# Laser_Array_Temp_Low_BRD_V2_3.net
KiCad netlist of a schematic drawn in EAGLE
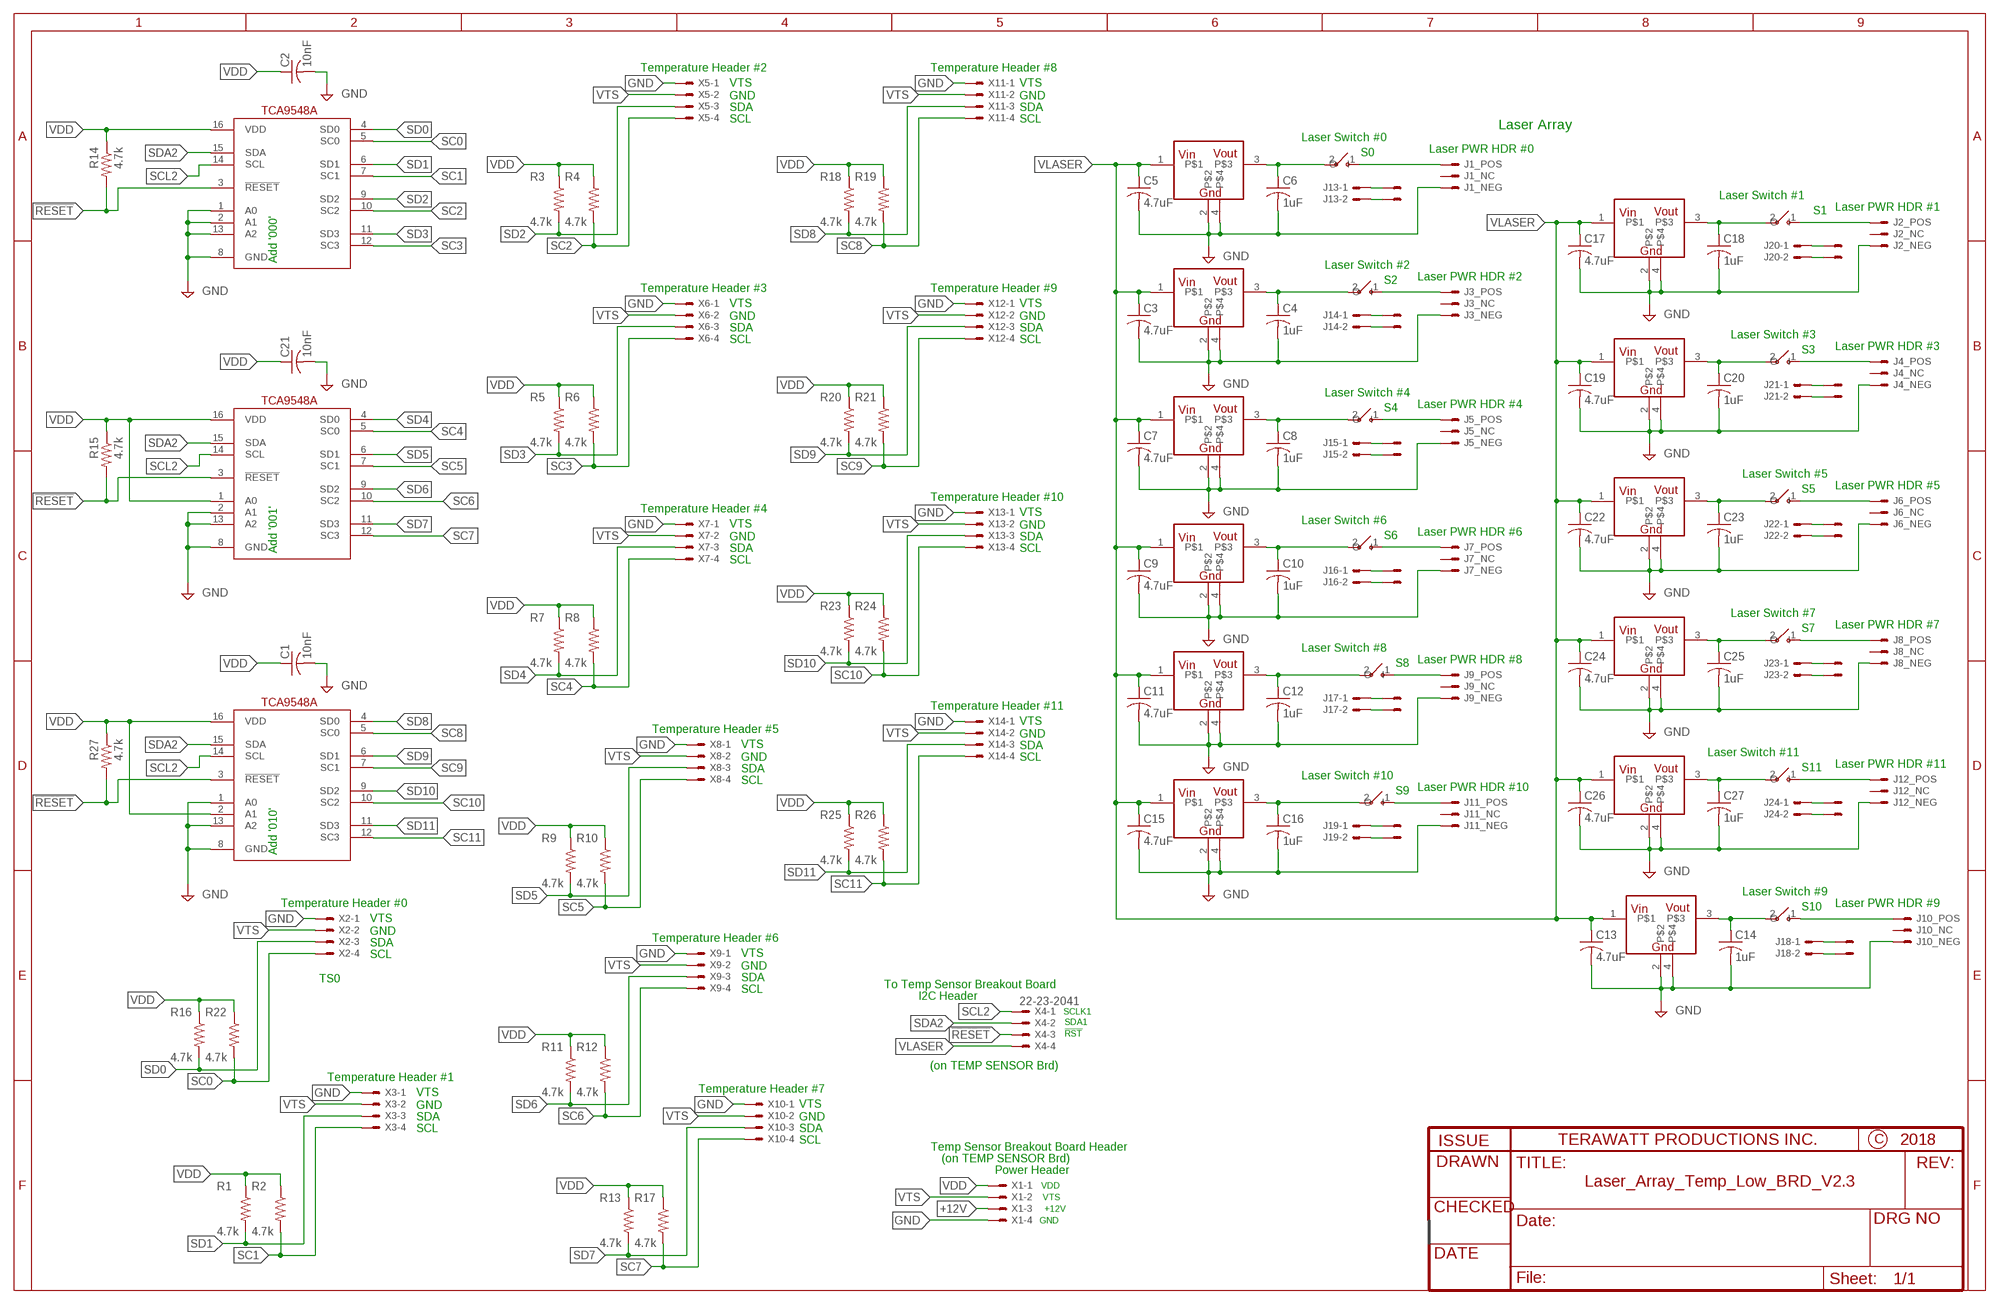
[diagram p0: schematic, sheet 1]

(export (version "E")
  (design (tool "Eeschema 10.0.6"))
  (components
    (comp (ref "C1")
      (value "10nF")
      (footprint "eagle-import:C0805")
      (libsource (lib "eagle-import") (part "C-USC0805"))
    )
    (comp (ref "C2")
      (value "10nF")
      (footprint "eagle-import:C0805")
      (libsource (lib "eagle-import") (part "C-USC0805"))
    )
    (comp (ref "C3")
      (value "4.7uF")
      (footprint "eagle-import:C0805")
      (libsource (lib "eagle-import") (part "C-USC0805"))
    )
    (comp (ref "C4")
      (value "1uF")
      (footprint "eagle-import:C0805")
      (libsource (lib "eagle-import") (part "C-USC0805"))
    )
    (comp (ref "C5")
      (value "4.7uF")
      (footprint "eagle-import:C0805")
      (libsource (lib "eagle-import") (part "C-USC0805"))
    )
    (comp (ref "C6")
      (value "1uF")
      (footprint "eagle-import:C0805")
      (libsource (lib "eagle-import") (part "C-USC0805"))
    )
    (comp (ref "C7")
      (value "4.7uF")
      (footprint "eagle-import:C0805")
      (libsource (lib "eagle-import") (part "C-USC0805"))
    )
    (comp (ref "C8")
      (value "1uF")
      (footprint "eagle-import:C0805")
      (libsource (lib "eagle-import") (part "C-USC0805"))
    )
    (comp (ref "C9")
      (value "4.7uF")
      (footprint "eagle-import:C0805")
      (libsource (lib "eagle-import") (part "C-USC0805"))
    )
    (comp (ref "C10")
      (value "1uF")
      (footprint "eagle-import:C0805")
      (libsource (lib "eagle-import") (part "C-USC0805"))
    )
    (comp (ref "C11")
      (value "4.7uF")
      (footprint "eagle-import:C0805")
      (libsource (lib "eagle-import") (part "C-USC0805"))
    )
    (comp (ref "C12")
      (value "1uF")
      (footprint "eagle-import:C0805")
      (libsource (lib "eagle-import") (part "C-USC0805"))
    )
    (comp (ref "C13")
      (value "4.7uF")
      (footprint "eagle-import:C0805")
      (libsource (lib "eagle-import") (part "C-USC0805"))
    )
    (comp (ref "C14")
      (value "1uF")
      (footprint "eagle-import:C0805")
      (libsource (lib "eagle-import") (part "C-USC0805"))
    )
    (comp (ref "C15")
      (value "4.7uF")
      (footprint "eagle-import:C0805")
      (libsource (lib "eagle-import") (part "C-USC0805"))
    )
    (comp (ref "C16")
      (value "1uF")
      (footprint "eagle-import:C0805")
      (libsource (lib "eagle-import") (part "C-USC0805"))
    )
    (comp (ref "C17")
      (value "4.7uF")
      (footprint "eagle-import:C0805")
      (libsource (lib "eagle-import") (part "C-USC0805"))
    )
    (comp (ref "C18")
      (value "1uF")
      (footprint "eagle-import:C0805")
      (libsource (lib "eagle-import") (part "C-USC0805"))
    )
    (comp (ref "C19")
      (value "4.7uF")
      (footprint "eagle-import:C0805")
      (libsource (lib "eagle-import") (part "C-USC0805"))
    )
    (comp (ref "C20")
      (value "1uF")
      (footprint "eagle-import:C0805")
      (libsource (lib "eagle-import") (part "C-USC0805"))
    )
    (comp (ref "C21")
      (value "10nF")
      (footprint "eagle-import:C0805")
      (libsource (lib "eagle-import") (part "C-USC0805"))
    )
    (comp (ref "C22")
      (value "4.7uF")
      (footprint "eagle-import:C0805")
      (libsource (lib "eagle-import") (part "C-USC0805"))
    )
    (comp (ref "C23")
      (value "1uF")
      (footprint "eagle-import:C0805")
      (libsource (lib "eagle-import") (part "C-USC0805"))
    )
    (comp (ref "C24")
      (value "4.7uF")
      (footprint "eagle-import:C0805")
      (libsource (lib "eagle-import") (part "C-USC0805"))
    )
    (comp (ref "C25")
      (value "1uF")
      (footprint "eagle-import:C0805")
      (libsource (lib "eagle-import") (part "C-USC0805"))
    )
    (comp (ref "C26")
      (value "4.7uF")
      (footprint "eagle-import:C0805")
      (libsource (lib "eagle-import") (part "C-USC0805"))
    )
    (comp (ref "C27")
      (value "1uF")
      (footprint "eagle-import:C0805")
      (libsource (lib "eagle-import") (part "C-USC0805"))
    )
    (comp (ref "J1")
      (value "LASER_MOD")
      (footprint "eagle-import:LASER_MOD")
      (libsource (lib "eagle-import") (part "LASER_MOD"))
    )
    (comp (ref "J2")
      (value "LASER_MOD")
      (footprint "eagle-import:LASER_MOD")
      (libsource (lib "eagle-import") (part "LASER_MOD"))
    )
    (comp (ref "J3")
      (value "LASER_MOD")
      (footprint "eagle-import:LASER_MOD")
      (libsource (lib "eagle-import") (part "LASER_MOD"))
    )
    (comp (ref "J4")
      (value "LASER_MOD")
      (footprint "eagle-import:LASER_MOD")
      (libsource (lib "eagle-import") (part "LASER_MOD"))
    )
    (comp (ref "J5")
      (value "LASER_MOD")
      (footprint "eagle-import:LASER_MOD")
      (libsource (lib "eagle-import") (part "LASER_MOD"))
    )
    (comp (ref "J6")
      (value "LASER_MOD")
      (footprint "eagle-import:LASER_MOD")
      (libsource (lib "eagle-import") (part "LASER_MOD"))
    )
    (comp (ref "J7")
      (value "LASER_MOD")
      (footprint "eagle-import:LASER_MOD")
      (libsource (lib "eagle-import") (part "LASER_MOD"))
    )
    (comp (ref "J8")
      (value "LASER_MOD")
      (footprint "eagle-import:LASER_MOD")
      (libsource (lib "eagle-import") (part "LASER_MOD"))
    )
    (comp (ref "J9")
      (value "LASER_MOD")
      (footprint "eagle-import:LASER_MOD")
      (libsource (lib "eagle-import") (part "LASER_MOD"))
    )
    (comp (ref "J10")
      (value "LASER_MOD")
      (footprint "eagle-import:LASER_MOD")
      (libsource (lib "eagle-import") (part "LASER_MOD"))
    )
    (comp (ref "J11")
      (value "LASER_MOD")
      (footprint "eagle-import:LASER_MOD")
      (libsource (lib "eagle-import") (part "LASER_MOD"))
    )
    (comp (ref "J12")
      (value "LASER_MOD")
      (footprint "eagle-import:LASER_MOD")
      (libsource (lib "eagle-import") (part "LASER_MOD"))
    )
    (comp (ref "J13")
      (value "22-23-2021")
      (footprint "eagle-import:22-23-2021")
      (fields (field (name "MF") "MOLEX"))
      (libsource (lib "eagle-import") (part "22-23-2021"))
    )
    (comp (ref "J14")
      (value "22-23-2021")
      (footprint "eagle-import:22-23-2021")
      (fields (field (name "MF") "MOLEX"))
      (libsource (lib "eagle-import") (part "22-23-2021"))
    )
    (comp (ref "J15")
      (value "22-23-2021")
      (footprint "eagle-import:22-23-2021")
      (fields (field (name "MF") "MOLEX"))
      (libsource (lib "eagle-import") (part "22-23-2021"))
    )
    (comp (ref "J16")
      (value "22-23-2021")
      (footprint "eagle-import:22-23-2021")
      (fields (field (name "MF") "MOLEX"))
      (libsource (lib "eagle-import") (part "22-23-2021"))
    )
    (comp (ref "J17")
      (value "22-23-2021")
      (footprint "eagle-import:22-23-2021")
      (fields (field (name "MF") "MOLEX"))
      (libsource (lib "eagle-import") (part "22-23-2021"))
    )
    (comp (ref "J18")
      (value "22-23-2021")
      (footprint "eagle-import:22-23-2021")
      (fields (field (name "MF") "MOLEX"))
      (libsource (lib "eagle-import") (part "22-23-2021"))
    )
    (comp (ref "J19")
      (value "22-23-2021")
      (footprint "eagle-import:22-23-2021")
      (fields (field (name "MF") "MOLEX"))
      (libsource (lib "eagle-import") (part "22-23-2021"))
    )
    (comp (ref "J20")
      (value "22-23-2021")
      (footprint "eagle-import:22-23-2021")
      (fields (field (name "MF") "MOLEX"))
      (libsource (lib "eagle-import") (part "22-23-2021"))
    )
    (comp (ref "J21")
      (value "22-23-2021")
      (footprint "eagle-import:22-23-2021")
      (fields (field (name "MF") "MOLEX"))
      (libsource (lib "eagle-import") (part "22-23-2021"))
    )
    (comp (ref "J22")
      (value "22-23-2021")
      (footprint "eagle-import:22-23-2021")
      (fields (field (name "MF") "MOLEX"))
      (libsource (lib "eagle-import") (part "22-23-2021"))
    )
    (comp (ref "J23")
      (value "22-23-2021")
      (footprint "eagle-import:22-23-2021")
      (fields (field (name "MF") "MOLEX"))
      (libsource (lib "eagle-import") (part "22-23-2021"))
    )
    (comp (ref "J24")
      (value "22-23-2021")
      (footprint "eagle-import:22-23-2021")
      (fields (field (name "MF") "MOLEX"))
      (libsource (lib "eagle-import") (part "22-23-2021"))
    )
    (comp (ref "R1")
      (value "4.7k")
      (footprint "eagle-import:M0805")
      (libsource (lib "eagle-import") (part "R-US_M0805"))
    )
    (comp (ref "R2")
      (value "4.7k")
      (footprint "eagle-import:M0805")
      (libsource (lib "eagle-import") (part "R-US_M0805"))
    )
    (comp (ref "R3")
      (value "4.7k")
      (footprint "eagle-import:M0805")
      (libsource (lib "eagle-import") (part "R-US_M0805"))
    )
    (comp (ref "R4")
      (value "4.7k")
      (footprint "eagle-import:M0805")
      (libsource (lib "eagle-import") (part "R-US_M0805"))
    )
    (comp (ref "R5")
      (value "4.7k")
      (footprint "eagle-import:M0805")
      (libsource (lib "eagle-import") (part "R-US_M0805"))
    )
    (comp (ref "R6")
      (value "4.7k")
      (footprint "eagle-import:M0805")
      (libsource (lib "eagle-import") (part "R-US_M0805"))
    )
    (comp (ref "R7")
      (value "4.7k")
      (footprint "eagle-import:M0805")
      (libsource (lib "eagle-import") (part "R-US_M0805"))
    )
    (comp (ref "R8")
      (value "4.7k")
      (footprint "eagle-import:M0805")
      (libsource (lib "eagle-import") (part "R-US_M0805"))
    )
    (comp (ref "R9")
      (value "4.7k")
      (footprint "eagle-import:M0805")
      (libsource (lib "eagle-import") (part "R-US_M0805"))
    )
    (comp (ref "R10")
      (value "4.7k")
      (footprint "eagle-import:M0805")
      (libsource (lib "eagle-import") (part "R-US_M0805"))
    )
    (comp (ref "R11")
      (value "4.7k")
      (footprint "eagle-import:M0805")
      (libsource (lib "eagle-import") (part "R-US_M0805"))
    )
    (comp (ref "R12")
      (value "4.7k")
      (footprint "eagle-import:M0805")
      (libsource (lib "eagle-import") (part "R-US_M0805"))
    )
    (comp (ref "R13")
      (value "4.7k")
      (footprint "eagle-import:M0805")
      (libsource (lib "eagle-import") (part "R-US_M0805"))
    )
    (comp (ref "R14")
      (value "4.7k")
      (footprint "eagle-import:M0805")
      (libsource (lib "eagle-import") (part "R-US_M0805"))
    )
    (comp (ref "R15")
      (value "4.7k")
      (footprint "eagle-import:M0805")
      (libsource (lib "eagle-import") (part "R-US_M0805"))
    )
    (comp (ref "R16")
      (value "4.7k")
      (footprint "eagle-import:M0805")
      (libsource (lib "eagle-import") (part "R-US_M0805"))
    )
    (comp (ref "R17")
      (value "4.7k")
      (footprint "eagle-import:M0805")
      (libsource (lib "eagle-import") (part "R-US_M0805"))
    )
    (comp (ref "R18")
      (value "4.7k")
      (footprint "eagle-import:M0805")
      (libsource (lib "eagle-import") (part "R-US_M0805"))
    )
    (comp (ref "R19")
      (value "4.7k")
      (footprint "eagle-import:M0805")
      (libsource (lib "eagle-import") (part "R-US_M0805"))
    )
    (comp (ref "R20")
      (value "4.7k")
      (footprint "eagle-import:M0805")
      (libsource (lib "eagle-import") (part "R-US_M0805"))
    )
    (comp (ref "R21")
      (value "4.7k")
      (footprint "eagle-import:M0805")
      (libsource (lib "eagle-import") (part "R-US_M0805"))
    )
    (comp (ref "R22")
      (value "4.7k")
      (footprint "eagle-import:M0805")
      (libsource (lib "eagle-import") (part "R-US_M0805"))
    )
    (comp (ref "R23")
      (value "4.7k")
      (footprint "eagle-import:M0805")
      (libsource (lib "eagle-import") (part "R-US_M0805"))
    )
    (comp (ref "R24")
      (value "4.7k")
      (footprint "eagle-import:M0805")
      (libsource (lib "eagle-import") (part "R-US_M0805"))
    )
    (comp (ref "R25")
      (value "4.7k")
      (footprint "eagle-import:M0805")
      (libsource (lib "eagle-import") (part "R-US_M0805"))
    )
    (comp (ref "R26")
      (value "4.7k")
      (footprint "eagle-import:M0805")
      (libsource (lib "eagle-import") (part "R-US_M0805"))
    )
    (comp (ref "R27")
      (value "4.7k")
      (footprint "eagle-import:M0805")
      (libsource (lib "eagle-import") (part "R-US_M0805"))
    )
    (comp (ref "S13")
      (value "TOGGLE_SPST")
      (footprint "eagle-import:22-23-2021")
      (libsource (lib "eagle-import") (part "TOGGLE_SPST"))
    )
    (comp (ref "S14")
      (value "TOGGLE_SPST")
      (footprint "eagle-import:22-23-2021")
      (libsource (lib "eagle-import") (part "TOGGLE_SPST"))
    )
    (comp (ref "S15")
      (value "TOGGLE_SPST")
      (footprint "eagle-import:22-23-2021")
      (libsource (lib "eagle-import") (part "TOGGLE_SPST"))
    )
    (comp (ref "S16")
      (value "TOGGLE_SPST")
      (footprint "eagle-import:22-23-2021")
      (libsource (lib "eagle-import") (part "TOGGLE_SPST"))
    )
    (comp (ref "S17")
      (value "TOGGLE_SPST")
      (footprint "eagle-import:22-23-2021")
      (libsource (lib "eagle-import") (part "TOGGLE_SPST"))
    )
    (comp (ref "S18")
      (value "TOGGLE_SPST")
      (footprint "eagle-import:22-23-2021")
      (libsource (lib "eagle-import") (part "TOGGLE_SPST"))
    )
    (comp (ref "S19")
      (value "TOGGLE_SPST")
      (footprint "eagle-import:22-23-2021")
      (libsource (lib "eagle-import") (part "TOGGLE_SPST"))
    )
    (comp (ref "S20")
      (value "TOGGLE_SPST")
      (footprint "eagle-import:22-23-2021")
      (libsource (lib "eagle-import") (part "TOGGLE_SPST"))
    )
    (comp (ref "S21")
      (value "TOGGLE_SPST")
      (footprint "eagle-import:22-23-2021")
      (libsource (lib "eagle-import") (part "TOGGLE_SPST"))
    )
    (comp (ref "S22")
      (value "TOGGLE_SPST")
      (footprint "eagle-import:22-23-2021")
      (libsource (lib "eagle-import") (part "TOGGLE_SPST"))
    )
    (comp (ref "S23")
      (value "TOGGLE_SPST")
      (footprint "eagle-import:22-23-2021")
      (libsource (lib "eagle-import") (part "TOGGLE_SPST"))
    )
    (comp (ref "S24")
      (value "TOGGLE_SPST")
      (footprint "eagle-import:22-23-2021")
      (libsource (lib "eagle-import") (part "TOGGLE_SPST"))
    )
    (comp (ref "U$1")
      (value "SINGLE_PAD")
      (footprint "eagle-import:SINGLE_PAD")
      (libsource (lib "eagle-import") (part "SINGLE_PAD"))
    )
    (comp (ref "U$2")
      (value "SINGLE_PAD")
      (footprint "eagle-import:SINGLE_PAD")
      (libsource (lib "eagle-import") (part "SINGLE_PAD"))
    )
    (comp (ref "U$4")
      (value "SINGLE_PAD")
      (footprint "eagle-import:SINGLE_PAD")
      (libsource (lib "eagle-import") (part "SINGLE_PAD"))
    )
    (comp (ref "U$5")
      (value "SINGLE_PAD")
      (footprint "eagle-import:SINGLE_PAD")
      (libsource (lib "eagle-import") (part "SINGLE_PAD"))
    )
    (comp (ref "U$7")
      (value "SINGLE_PAD")
      (footprint "eagle-import:SINGLE_PAD")
      (libsource (lib "eagle-import") (part "SINGLE_PAD"))
    )
    (comp (ref "U$8")
      (value "SINGLE_PAD")
      (footprint "eagle-import:SINGLE_PAD")
      (libsource (lib "eagle-import") (part "SINGLE_PAD"))
    )
    (comp (ref "U$10")
      (value "SINGLE_PAD")
      (footprint "eagle-import:SINGLE_PAD")
      (libsource (lib "eagle-import") (part "SINGLE_PAD"))
    )
    (comp (ref "U$11")
      (value "SINGLE_PAD")
      (footprint "eagle-import:SINGLE_PAD")
      (libsource (lib "eagle-import") (part "SINGLE_PAD"))
    )
    (comp (ref "U$13")
      (value "SINGLE_PAD")
      (footprint "eagle-import:SINGLE_PAD")
      (libsource (lib "eagle-import") (part "SINGLE_PAD"))
    )
    (comp (ref "U$14")
      (value "SINGLE_PAD")
      (footprint "eagle-import:SINGLE_PAD")
      (libsource (lib "eagle-import") (part "SINGLE_PAD"))
    )
    (comp (ref "U$16")
      (value "SINGLE_PAD")
      (footprint "eagle-import:SINGLE_PAD")
      (libsource (lib "eagle-import") (part "SINGLE_PAD"))
    )
    (comp (ref "U$17")
      (value "SINGLE_PAD")
      (footprint "eagle-import:SINGLE_PAD")
      (libsource (lib "eagle-import") (part "SINGLE_PAD"))
    )
    (comp (ref "U$19")
      (value "SINGLE_PAD")
      (footprint "eagle-import:SINGLE_PAD")
      (libsource (lib "eagle-import") (part "SINGLE_PAD"))
    )
    (comp (ref "U$20")
      (value "SINGLE_PAD")
      (footprint "eagle-import:SINGLE_PAD")
      (libsource (lib "eagle-import") (part "SINGLE_PAD"))
    )
    (comp (ref "U$22")
      (value "SINGLE_PAD")
      (footprint "eagle-import:SINGLE_PAD")
      (libsource (lib "eagle-import") (part "SINGLE_PAD"))
    )
    (comp (ref "U$23")
      (value "SINGLE_PAD")
      (footprint "eagle-import:SINGLE_PAD")
      (libsource (lib "eagle-import") (part "SINGLE_PAD"))
    )
    (comp (ref "U$25")
      (value "SINGLE_PAD")
      (footprint "eagle-import:SINGLE_PAD")
      (libsource (lib "eagle-import") (part "SINGLE_PAD"))
    )
    (comp (ref "U$26")
      (value "SINGLE_PAD")
      (footprint "eagle-import:SINGLE_PAD")
      (libsource (lib "eagle-import") (part "SINGLE_PAD"))
    )
    (comp (ref "U$28")
      (value "SINGLE_PAD")
      (footprint "eagle-import:SINGLE_PAD")
      (libsource (lib "eagle-import") (part "SINGLE_PAD"))
    )
    (comp (ref "U$29")
      (value "SINGLE_PAD")
      (footprint "eagle-import:SINGLE_PAD")
      (libsource (lib "eagle-import") (part "SINGLE_PAD"))
    )
    (comp (ref "U$31")
      (value "SINGLE_PAD")
      (footprint "eagle-import:SINGLE_PAD")
      (libsource (lib "eagle-import") (part "SINGLE_PAD"))
    )
    (comp (ref "U$32")
      (value "SINGLE_PAD")
      (footprint "eagle-import:SINGLE_PAD")
      (libsource (lib "eagle-import") (part "SINGLE_PAD"))
    )
    (comp (ref "U$34")
      (value "SINGLE_PAD")
      (footprint "eagle-import:SINGLE_PAD")
      (libsource (lib "eagle-import") (part "SINGLE_PAD"))
    )
    (comp (ref "U$35")
      (value "SINGLE_PAD")
      (footprint "eagle-import:SINGLE_PAD")
      (libsource (lib "eagle-import") (part "SINGLE_PAD"))
    )
    (comp (ref "U1")
      (value "TCA9546A")
      (footprint "eagle-import:SOIC16N")
      (libsource (lib "eagle-import") (part "TCA9546A"))
    )
    (comp (ref "U2")
      (value "TCA9546A")
      (footprint "eagle-import:SOIC16N")
      (libsource (lib "eagle-import") (part "TCA9546A"))
    )
    (comp (ref "U3")
      (value "TCA9546A")
      (footprint "eagle-import:SOIC16N")
      (libsource (lib "eagle-import") (part "TCA9546A"))
    )
    (comp (ref "U4")
      (value "V_REG_3.0V_1.0A")
      (footprint "eagle-import:SOT223")
      (libsource (lib "eagle-import") (part "V_REG_3.0V_1.0A"))
    )
    (comp (ref "U5")
      (value "V_REG_3.0V_1.0A")
      (footprint "eagle-import:SOT223")
      (libsource (lib "eagle-import") (part "V_REG_3.0V_1.0A"))
    )
    (comp (ref "U6")
      (value "V_REG_3.0V_1.0A")
      (footprint "eagle-import:SOT223")
      (libsource (lib "eagle-import") (part "V_REG_3.0V_1.0A"))
    )
    (comp (ref "U7")
      (value "V_REG_3.0V_1.0A")
      (footprint "eagle-import:SOT223")
      (libsource (lib "eagle-import") (part "V_REG_3.0V_1.0A"))
    )
    (comp (ref "U8")
      (value "V_REG_3.0V_1.0A")
      (footprint "eagle-import:SOT223")
      (libsource (lib "eagle-import") (part "V_REG_3.0V_1.0A"))
    )
    (comp (ref "U9")
      (value "V_REG_3.0V_1.0A")
      (footprint "eagle-import:SOT223")
      (libsource (lib "eagle-import") (part "V_REG_3.0V_1.0A"))
    )
    (comp (ref "U10")
      (value "V_REG_3.0V_1.0A")
      (footprint "eagle-import:SOT223")
      (libsource (lib "eagle-import") (part "V_REG_3.0V_1.0A"))
    )
    (comp (ref "U11")
      (value "V_REG_3.0V_1.0A")
      (footprint "eagle-import:SOT223")
      (libsource (lib "eagle-import") (part "V_REG_3.0V_1.0A"))
    )
    (comp (ref "U12")
      (value "V_REG_3.0V_1.0A")
      (footprint "eagle-import:SOT223")
      (libsource (lib "eagle-import") (part "V_REG_3.0V_1.0A"))
    )
    (comp (ref "U13")
      (value "V_REG_3.0V_1.0A")
      (footprint "eagle-import:SOT223")
      (libsource (lib "eagle-import") (part "V_REG_3.0V_1.0A"))
    )
    (comp (ref "U14")
      (value "V_REG_3.0V_1.0A")
      (footprint "eagle-import:SOT223")
      (libsource (lib "eagle-import") (part "V_REG_3.0V_1.0A"))
    )
    (comp (ref "U15")
      (value "V_REG_3.0V_1.0A")
      (footprint "eagle-import:SOT223")
      (libsource (lib "eagle-import") (part "V_REG_3.0V_1.0A"))
    )
    (comp (ref "X1")
      (value "22-23-2041")
      (footprint "eagle-import:22-23-2041")
      (fields (field (name "MF") "MOLEX"))
      (libsource (lib "eagle-import") (part "22-23-2041"))
    )
    (comp (ref "X2")
      (value "22-23-2041")
      (footprint "eagle-import:22-23-2041")
      (fields (field (name "MF") "MOLEX"))
      (libsource (lib "eagle-import") (part "22-23-2041"))
    )
    (comp (ref "X3")
      (value "22-23-2041")
      (footprint "eagle-import:22-23-2041")
      (fields (field (name "MF") "MOLEX"))
      (libsource (lib "eagle-import") (part "22-23-2041"))
    )
    (comp (ref "X4")
      (value "22-23-2041")
      (footprint "eagle-import:22-23-2041")
      (fields (field (name "MF") "MOLEX"))
      (libsource (lib "eagle-import") (part "22-23-2041"))
    )
    (comp (ref "X5")
      (value "22-23-2041")
      (footprint "eagle-import:22-23-2041")
      (fields (field (name "MF") "MOLEX"))
      (libsource (lib "eagle-import") (part "22-23-2041"))
    )
    (comp (ref "X6")
      (value "22-23-2041")
      (footprint "eagle-import:22-23-2041")
      (fields (field (name "MF") "MOLEX"))
      (libsource (lib "eagle-import") (part "22-23-2041"))
    )
    (comp (ref "X7")
      (value "22-23-2041")
      (footprint "eagle-import:22-23-2041")
      (fields (field (name "MF") "MOLEX"))
      (libsource (lib "eagle-import") (part "22-23-2041"))
    )
    (comp (ref "X8")
      (value "22-23-2041")
      (footprint "eagle-import:22-23-2041")
      (fields (field (name "MF") "MOLEX"))
      (libsource (lib "eagle-import") (part "22-23-2041"))
    )
    (comp (ref "X9")
      (value "22-23-2041")
      (footprint "eagle-import:22-23-2041")
      (fields (field (name "MF") "MOLEX"))
      (libsource (lib "eagle-import") (part "22-23-2041"))
    )
    (comp (ref "X10")
      (value "22-23-2041")
      (footprint "eagle-import:22-23-2041")
      (fields (field (name "MF") "MOLEX"))
      (libsource (lib "eagle-import") (part "22-23-2041"))
    )
    (comp (ref "X11")
      (value "22-23-2041")
      (footprint "eagle-import:22-23-2041")
      (fields (field (name "MF") "MOLEX"))
      (libsource (lib "eagle-import") (part "22-23-2041"))
    )
    (comp (ref "X12")
      (value "22-23-2041")
      (footprint "eagle-import:22-23-2041")
      (fields (field (name "MF") "MOLEX"))
      (libsource (lib "eagle-import") (part "22-23-2041"))
    )
    (comp (ref "X13")
      (value "22-23-2041")
      (footprint "eagle-import:22-23-2041")
      (fields (field (name "MF") "MOLEX"))
      (libsource (lib "eagle-import") (part "22-23-2041"))
    )
    (comp (ref "X14")
      (value "22-23-2041")
      (footprint "eagle-import:22-23-2041")
      (fields (field (name "MF") "MOLEX"))
      (libsource (lib "eagle-import") (part "22-23-2041"))
    )
  )
  (nets
    (net (code "1") (name "+12V") (class "Default")
      (node (ref "X1") (pin "3") (pinfunction "S_3") (pintype "passive"))
    )
    (net (code "2") (name "/~{RESET}") (class "Default")
      (node (ref "R14") (pin "2") (pinfunction "2_2") (pintype "passive"))
      (node (ref "R15") (pin "2") (pinfunction "2_2") (pintype "passive"))
      (node (ref "R27") (pin "2") (pinfunction "2_2") (pintype "passive"))
      (node (ref "U1") (pin "3") (pinfunction "~{RESET}_3") (pintype "bidirectional"))
      (node (ref "U2") (pin "3") (pinfunction "~{RESET}_3") (pintype "bidirectional"))
      (node (ref "U3") (pin "3") (pinfunction "~{RESET}_3") (pintype "bidirectional"))
      (node (ref "X4") (pin "3") (pinfunction "S_3") (pintype "passive"))
    )
    (net (code "3") (name "GND") (class "Default")
      (node (ref "C1") (pin "2") (pinfunction "2_2") (pintype "passive"))
      (node (ref "C10") (pin "2") (pinfunction "2_2") (pintype "passive"))
      (node (ref "C11") (pin "2") (pinfunction "2_2") (pintype "passive"))
      (node (ref "C12") (pin "2") (pinfunction "2_2") (pintype "passive"))
      (node (ref "C13") (pin "2") (pinfunction "2_2") (pintype "passive"))
      (node (ref "C14") (pin "2") (pinfunction "2_2") (pintype "passive"))
      (node (ref "C15") (pin "2") (pinfunction "2_2") (pintype "passive"))
      (node (ref "C16") (pin "2") (pinfunction "2_2") (pintype "passive"))
      (node (ref "C17") (pin "2") (pinfunction "2_2") (pintype "passive"))
      (node (ref "C18") (pin "2") (pinfunction "2_2") (pintype "passive"))
      (node (ref "C19") (pin "2") (pinfunction "2_2") (pintype "passive"))
      (node (ref "C2") (pin "2") (pinfunction "2_2") (pintype "passive"))
      (node (ref "C20") (pin "2") (pinfunction "2_2") (pintype "passive"))
      (node (ref "C21") (pin "2") (pinfunction "2_2") (pintype "passive"))
      (node (ref "C22") (pin "2") (pinfunction "2_2") (pintype "passive"))
      (node (ref "C23") (pin "2") (pinfunction "2_2") (pintype "passive"))
      (node (ref "C24") (pin "2") (pinfunction "2_2") (pintype "passive"))
      (node (ref "C25") (pin "2") (pinfunction "2_2") (pintype "passive"))
      (node (ref "C26") (pin "2") (pinfunction "2_2") (pintype "passive"))
      (node (ref "C27") (pin "2") (pinfunction "2_2") (pintype "passive"))
      (node (ref "C3") (pin "2") (pinfunction "2_2") (pintype "passive"))
      (node (ref "C4") (pin "2") (pinfunction "2_2") (pintype "passive"))
      (node (ref "C5") (pin "2") (pinfunction "2_2") (pintype "passive"))
      (node (ref "C6") (pin "2") (pinfunction "2_2") (pintype "passive"))
      (node (ref "C7") (pin "2") (pinfunction "2_2") (pintype "passive"))
      (node (ref "C8") (pin "2") (pinfunction "2_2") (pintype "passive"))
      (node (ref "C9") (pin "2") (pinfunction "2_2") (pintype "passive"))
      (node (ref "J1") (pin "3") (pinfunction "S_3") (pintype "passive"))
      (node (ref "J10") (pin "3") (pinfunction "S_3") (pintype "passive"))
      (node (ref "J11") (pin "3") (pinfunction "S_3") (pintype "passive"))
      (node (ref "J12") (pin "3") (pinfunction "S_3") (pintype "passive"))
      (node (ref "J2") (pin "3") (pinfunction "S_3") (pintype "passive"))
      (node (ref "J3") (pin "3") (pinfunction "S_3") (pintype "passive"))
      (node (ref "J4") (pin "3") (pinfunction "S_3") (pintype "passive"))
      (node (ref "J5") (pin "3") (pinfunction "S_3") (pintype "passive"))
      (node (ref "J6") (pin "3") (pinfunction "S_3") (pintype "passive"))
      (node (ref "J7") (pin "3") (pinfunction "S_3") (pintype "passive"))
      (node (ref "J8") (pin "3") (pinfunction "S_3") (pintype "passive"))
      (node (ref "J9") (pin "3") (pinfunction "S_3") (pintype "passive"))
      (node (ref "U1") (pin "1") (pinfunction "A0_1") (pintype "bidirectional"))
      (node (ref "U1") (pin "13") (pinfunction "A2_13") (pintype "bidirectional"))
      (node (ref "U1") (pin "2") (pinfunction "A1_2") (pintype "bidirectional"))
      (node (ref "U1") (pin "8") (pinfunction "GND_8") (pintype "bidirectional"))
      (node (ref "U10") (pin "2") (pinfunction "P$2_2") (pintype "bidirectional"))
      (node (ref "U10") (pin "4") (pinfunction "P$4_4") (pintype "bidirectional"))
      (node (ref "U11") (pin "2") (pinfunction "P$2_2") (pintype "bidirectional"))
      (node (ref "U11") (pin "4") (pinfunction "P$4_4") (pintype "bidirectional"))
      (node (ref "U12") (pin "2") (pinfunction "P$2_2") (pintype "bidirectional"))
      (node (ref "U12") (pin "4") (pinfunction "P$4_4") (pintype "bidirectional"))
      (node (ref "U13") (pin "2") (pinfunction "P$2_2") (pintype "bidirectional"))
      (node (ref "U13") (pin "4") (pinfunction "P$4_4") (pintype "bidirectional"))
      (node (ref "U14") (pin "2") (pinfunction "P$2_2") (pintype "bidirectional"))
      (node (ref "U14") (pin "4") (pinfunction "P$4_4") (pintype "bidirectional"))
      (node (ref "U15") (pin "2") (pinfunction "P$2_2") (pintype "bidirectional"))
      (node (ref "U15") (pin "4") (pinfunction "P$4_4") (pintype "bidirectional"))
      (node (ref "U2") (pin "13") (pinfunction "A2_13") (pintype "bidirectional"))
      (node (ref "U2") (pin "2") (pinfunction "A1_2") (pintype "bidirectional"))
      (node (ref "U2") (pin "8") (pinfunction "GND_8") (pintype "bidirectional"))
      (node (ref "U3") (pin "1") (pinfunction "A0_1") (pintype "bidirectional"))
      (node (ref "U3") (pin "13") (pinfunction "A2_13") (pintype "bidirectional"))
      (node (ref "U3") (pin "8") (pinfunction "GND_8") (pintype "bidirectional"))
      (node (ref "U4") (pin "2") (pinfunction "P$2_2") (pintype "bidirectional"))
      (node (ref "U4") (pin "4") (pinfunction "P$4_4") (pintype "bidirectional"))
      (node (ref "U5") (pin "2") (pinfunction "P$2_2") (pintype "bidirectional"))
      (node (ref "U5") (pin "4") (pinfunction "P$4_4") (pintype "bidirectional"))
      (node (ref "U6") (pin "2") (pinfunction "P$2_2") (pintype "bidirectional"))
      (node (ref "U6") (pin "4") (pinfunction "P$4_4") (pintype "bidirectional"))
      (node (ref "U7") (pin "2") (pinfunction "P$2_2") (pintype "bidirectional"))
      (node (ref "U7") (pin "4") (pinfunction "P$4_4") (pintype "bidirectional"))
      (node (ref "U8") (pin "2") (pinfunction "P$2_2") (pintype "bidirectional"))
      (node (ref "U8") (pin "4") (pinfunction "P$4_4") (pintype "bidirectional"))
      (node (ref "U9") (pin "2") (pinfunction "P$2_2") (pintype "bidirectional"))
      (node (ref "U9") (pin "4") (pinfunction "P$4_4") (pintype "bidirectional"))
      (node (ref "X1") (pin "4") (pinfunction "S_4") (pintype "passive"))
      (node (ref "X10") (pin "1") (pinfunction "S_1") (pintype "passive"))
      (node (ref "X11") (pin "1") (pinfunction "S_1") (pintype "passive"))
      (node (ref "X12") (pin "1") (pinfunction "S_1") (pintype "passive"))
      (node (ref "X13") (pin "1") (pinfunction "S_1") (pintype "passive"))
      (node (ref "X14") (pin "1") (pinfunction "S_1") (pintype "passive"))
      (node (ref "X2") (pin "1") (pinfunction "S_1") (pintype "passive"))
      (node (ref "X3") (pin "1") (pinfunction "S_1") (pintype "passive"))
      (node (ref "X5") (pin "1") (pinfunction "S_1") (pintype "passive"))
      (node (ref "X6") (pin "1") (pinfunction "S_1") (pintype "passive"))
      (node (ref "X7") (pin "1") (pinfunction "S_1") (pintype "passive"))
      (node (ref "X8") (pin "1") (pinfunction "S_1") (pintype "passive"))
      (node (ref "X9") (pin "1") (pinfunction "S_1") (pintype "passive"))
    )
    (net (code "4") (name "Net-(J1C-S)") (class "Default")
      (node (ref "J1") (pin "1") (pinfunction "S_1") (pintype "passive"))
      (node (ref "S16") (pin "1") (pinfunction "O_1") (pintype "bidirectional"))
    )
    (net (code "5") (name "Net-(J2C-S)") (class "Default")
      (node (ref "J2") (pin "1") (pinfunction "S_1") (pintype "passive"))
      (node (ref "S13") (pin "1") (pinfunction "O_1") (pintype "bidirectional"))
    )
    (net (code "6") (name "Net-(J3C-S)") (class "Default")
      (node (ref "J3") (pin "1") (pinfunction "S_1") (pintype "passive"))
      (node (ref "S14") (pin "1") (pinfunction "O_1") (pintype "bidirectional"))
    )
    (net (code "7") (name "Net-(J4C-S)") (class "Default")
      (node (ref "J4") (pin "1") (pinfunction "S_1") (pintype "passive"))
      (node (ref "S15") (pin "1") (pinfunction "O_1") (pintype "bidirectional"))
    )
    (net (code "8") (name "Net-(J5C-S)") (class "Default")
      (node (ref "J5") (pin "1") (pinfunction "S_1") (pintype "passive"))
      (node (ref "S17") (pin "1") (pinfunction "O_1") (pintype "bidirectional"))
    )
    (net (code "9") (name "Net-(J6C-S)") (class "Default")
      (node (ref "J6") (pin "1") (pinfunction "S_1") (pintype "passive"))
      (node (ref "S18") (pin "1") (pinfunction "O_1") (pintype "bidirectional"))
    )
    (net (code "10") (name "Net-(J7C-S)") (class "Default")
      (node (ref "J7") (pin "1") (pinfunction "S_1") (pintype "passive"))
      (node (ref "S19") (pin "1") (pinfunction "O_1") (pintype "bidirectional"))
    )
    (net (code "11") (name "Net-(J8C-S)") (class "Default")
      (node (ref "J8") (pin "1") (pinfunction "S_1") (pintype "passive"))
      (node (ref "S20") (pin "1") (pinfunction "O_1") (pintype "bidirectional"))
    )
    (net (code "12") (name "Net-(J9C-S)") (class "Default")
      (node (ref "J9") (pin "1") (pinfunction "S_1") (pintype "passive"))
      (node (ref "S21") (pin "1") (pinfunction "O_1") (pintype "bidirectional"))
    )
    (net (code "13") (name "Net-(J10C-S)") (class "Default")
      (node (ref "J10") (pin "1") (pinfunction "S_1") (pintype "passive"))
      (node (ref "S22") (pin "1") (pinfunction "O_1") (pintype "bidirectional"))
    )
    (net (code "14") (name "Net-(J11C-S)") (class "Default")
      (node (ref "J11") (pin "1") (pinfunction "S_1") (pintype "passive"))
      (node (ref "S23") (pin "1") (pinfunction "O_1") (pintype "bidirectional"))
    )
    (net (code "15") (name "Net-(J12C-S)") (class "Default")
      (node (ref "J12") (pin "1") (pinfunction "S_1") (pintype "passive"))
      (node (ref "S24") (pin "1") (pinfunction "O_1") (pintype "bidirectional"))
    )
    (net (code "16") (name "Net-(J13A-S)") (class "Default")
      (node (ref "J13") (pin "1") (pinfunction "S_1") (pintype "passive"))
      (node (ref "U$1") (pin "1") (pinfunction "S_1") (pintype "passive"))
    )
    (net (code "17") (name "Net-(J13B-S)") (class "Default")
      (node (ref "J13") (pin "2") (pinfunction "S_2") (pintype "passive"))
      (node (ref "U$2") (pin "1") (pinfunction "S_1") (pintype "passive"))
    )
    (net (code "18") (name "Net-(J14A-S)") (class "Default")
      (node (ref "J14") (pin "1") (pinfunction "S_1") (pintype "passive"))
      (node (ref "U$4") (pin "1") (pinfunction "S_1") (pintype "passive"))
    )
    (net (code "19") (name "Net-(J14B-S)") (class "Default")
      (node (ref "J14") (pin "2") (pinfunction "S_2") (pintype "passive"))
      (node (ref "U$5") (pin "1") (pinfunction "S_1") (pintype "passive"))
    )
    (net (code "20") (name "Net-(J15A-S)") (class "Default")
      (node (ref "J15") (pin "1") (pinfunction "S_1") (pintype "passive"))
      (node (ref "U$13") (pin "1") (pinfunction "S_1") (pintype "passive"))
    )
    (net (code "21") (name "Net-(J15B-S)") (class "Default")
      (node (ref "J15") (pin "2") (pinfunction "S_2") (pintype "passive"))
      (node (ref "U$14") (pin "1") (pinfunction "S_1") (pintype "passive"))
    )
    (net (code "22") (name "Net-(J16A-S)") (class "Default")
      (node (ref "J16") (pin "1") (pinfunction "S_1") (pintype "passive"))
      (node (ref "U$19") (pin "1") (pinfunction "S_1") (pintype "passive"))
    )
    (net (code "23") (name "Net-(J16B-S)") (class "Default")
      (node (ref "J16") (pin "2") (pinfunction "S_2") (pintype "passive"))
      (node (ref "U$20") (pin "1") (pinfunction "S_1") (pintype "passive"))
    )
    (net (code "24") (name "Net-(J17A-S)") (class "Default")
      (node (ref "J17") (pin "1") (pinfunction "S_1") (pintype "passive"))
      (node (ref "U$25") (pin "1") (pinfunction "S_1") (pintype "passive"))
    )
    (net (code "25") (name "Net-(J17B-S)") (class "Default")
      (node (ref "J17") (pin "2") (pinfunction "S_2") (pintype "passive"))
      (node (ref "U$26") (pin "1") (pinfunction "S_1") (pintype "passive"))
    )
    (net (code "26") (name "Net-(J18A-S)") (class "Default")
      (node (ref "J18") (pin "1") (pinfunction "S_1") (pintype "passive"))
      (node (ref "U$28") (pin "1") (pinfunction "S_1") (pintype "passive"))
    )
    (net (code "27") (name "Net-(J18B-S)") (class "Default")
      (node (ref "J18") (pin "2") (pinfunction "S_2") (pintype "passive"))
      (node (ref "U$29") (pin "1") (pinfunction "S_1") (pintype "passive"))
    )
    (net (code "28") (name "Net-(J19A-S)") (class "Default")
      (node (ref "J19") (pin "1") (pinfunction "S_1") (pintype "passive"))
      (node (ref "U$34") (pin "1") (pinfunction "S_1") (pintype "passive"))
    )
    (net (code "29") (name "Net-(J19B-S)") (class "Default")
      (node (ref "J19") (pin "2") (pinfunction "S_2") (pintype "passive"))
      (node (ref "U$35") (pin "1") (pinfunction "S_1") (pintype "passive"))
    )
    (net (code "30") (name "Net-(J20A-S)") (class "Default")
      (node (ref "J20") (pin "1") (pinfunction "S_1") (pintype "passive"))
      (node (ref "U$7") (pin "1") (pinfunction "S_1") (pintype "passive"))
    )
    (net (code "31") (name "Net-(J20B-S)") (class "Default")
      (node (ref "J20") (pin "2") (pinfunction "S_2") (pintype "passive"))
      (node (ref "U$8") (pin "1") (pinfunction "S_1") (pintype "passive"))
    )
    (net (code "32") (name "Net-(J21A-S)") (class "Default")
      (node (ref "J21") (pin "1") (pinfunction "S_1") (pintype "passive"))
      (node (ref "U$10") (pin "1") (pinfunction "S_1") (pintype "passive"))
    )
    (net (code "33") (name "Net-(J21B-S)") (class "Default")
      (node (ref "J21") (pin "2") (pinfunction "S_2") (pintype "passive"))
      (node (ref "U$11") (pin "1") (pinfunction "S_1") (pintype "passive"))
    )
    (net (code "34") (name "Net-(J22A-S)") (class "Default")
      (node (ref "J22") (pin "1") (pinfunction "S_1") (pintype "passive"))
      (node (ref "U$16") (pin "1") (pinfunction "S_1") (pintype "passive"))
    )
    (net (code "35") (name "Net-(J22B-S)") (class "Default")
      (node (ref "J22") (pin "2") (pinfunction "S_2") (pintype "passive"))
      (node (ref "U$17") (pin "1") (pinfunction "S_1") (pintype "passive"))
    )
    (net (code "36") (name "Net-(J23A-S)") (class "Default")
      (node (ref "J23") (pin "1") (pinfunction "S_1") (pintype "passive"))
      (node (ref "U$22") (pin "1") (pinfunction "S_1") (pintype "passive"))
    )
    (net (code "37") (name "Net-(J23B-S)") (class "Default")
      (node (ref "J23") (pin "2") (pinfunction "S_2") (pintype "passive"))
      (node (ref "U$23") (pin "1") (pinfunction "S_1") (pintype "passive"))
    )
    (net (code "38") (name "Net-(J24A-S)") (class "Default")
      (node (ref "J24") (pin "1") (pinfunction "S_1") (pintype "passive"))
      (node (ref "U$31") (pin "1") (pinfunction "S_1") (pintype "passive"))
    )
    (net (code "39") (name "Net-(J24B-S)") (class "Default")
      (node (ref "J24") (pin "2") (pinfunction "S_2") (pintype "passive"))
      (node (ref "U$32") (pin "1") (pinfunction "S_1") (pintype "passive"))
    )
    (net (code "40") (name "Net-(S13-I)") (class "Default")
      (node (ref "C18") (pin "1") (pinfunction "1_1") (pintype "passive"))
      (node (ref "S13") (pin "2") (pinfunction "I_2") (pintype "bidirectional"))
      (node (ref "U11") (pin "3") (pinfunction "P$3_3") (pintype "bidirectional"))
    )
    (net (code "41") (name "Net-(S14-I)") (class "Default")
      (node (ref "C4") (pin "1") (pinfunction "1_1") (pintype "passive"))
      (node (ref "S14") (pin "2") (pinfunction "I_2") (pintype "bidirectional"))
      (node (ref "U4") (pin "3") (pinfunction "P$3_3") (pintype "bidirectional"))
    )
    (net (code "42") (name "Net-(S15-I)") (class "Default")
      (node (ref "C20") (pin "1") (pinfunction "1_1") (pintype "passive"))
      (node (ref "S15") (pin "2") (pinfunction "I_2") (pintype "bidirectional"))
      (node (ref "U12") (pin "3") (pinfunction "P$3_3") (pintype "bidirectional"))
    )
    (net (code "43") (name "Net-(S16-I)") (class "Default")
      (node (ref "C6") (pin "1") (pinfunction "1_1") (pintype "passive"))
      (node (ref "S16") (pin "2") (pinfunction "I_2") (pintype "bidirectional"))
      (node (ref "U5") (pin "3") (pinfunction "P$3_3") (pintype "bidirectional"))
    )
    (net (code "44") (name "Net-(S17-I)") (class "Default")
      (node (ref "C8") (pin "1") (pinfunction "1_1") (pintype "passive"))
      (node (ref "S17") (pin "2") (pinfunction "I_2") (pintype "bidirectional"))
      (node (ref "U6") (pin "3") (pinfunction "P$3_3") (pintype "bidirectional"))
    )
    (net (code "45") (name "Net-(S18-I)") (class "Default")
      (node (ref "C23") (pin "1") (pinfunction "1_1") (pintype "passive"))
      (node (ref "S18") (pin "2") (pinfunction "I_2") (pintype "bidirectional"))
      (node (ref "U13") (pin "3") (pinfunction "P$3_3") (pintype "bidirectional"))
    )
    (net (code "46") (name "Net-(S19-I)") (class "Default")
      (node (ref "C10") (pin "1") (pinfunction "1_1") (pintype "passive"))
      (node (ref "S19") (pin "2") (pinfunction "I_2") (pintype "bidirectional"))
      (node (ref "U7") (pin "3") (pinfunction "P$3_3") (pintype "bidirectional"))
    )
    (net (code "47") (name "Net-(S20-I)") (class "Default")
      (node (ref "C25") (pin "1") (pinfunction "1_1") (pintype "passive"))
      (node (ref "S20") (pin "2") (pinfunction "I_2") (pintype "bidirectional"))
      (node (ref "U14") (pin "3") (pinfunction "P$3_3") (pintype "bidirectional"))
    )
    (net (code "48") (name "Net-(S21-I)") (class "Default")
      (node (ref "C12") (pin "1") (pinfunction "1_1") (pintype "passive"))
      (node (ref "S21") (pin "2") (pinfunction "I_2") (pintype "bidirectional"))
      (node (ref "U8") (pin "3") (pinfunction "P$3_3") (pintype "bidirectional"))
    )
    (net (code "49") (name "Net-(S22-I)") (class "Default")
      (node (ref "C14") (pin "1") (pinfunction "1_1") (pintype "passive"))
      (node (ref "S22") (pin "2") (pinfunction "I_2") (pintype "bidirectional"))
      (node (ref "U9") (pin "3") (pinfunction "P$3_3") (pintype "bidirectional"))
    )
    (net (code "50") (name "Net-(S23-I)") (class "Default")
      (node (ref "C16") (pin "1") (pinfunction "1_1") (pintype "passive"))
      (node (ref "S23") (pin "2") (pinfunction "I_2") (pintype "bidirectional"))
      (node (ref "U10") (pin "3") (pinfunction "P$3_3") (pintype "bidirectional"))
    )
    (net (code "51") (name "Net-(S24-I)") (class "Default")
      (node (ref "C27") (pin "1") (pinfunction "1_1") (pintype "passive"))
      (node (ref "S24") (pin "2") (pinfunction "I_2") (pintype "bidirectional"))
      (node (ref "U15") (pin "3") (pinfunction "P$3_3") (pintype "bidirectional"))
    )
    (net (code "52") (name "SC0") (class "Default")
      (node (ref "R22") (pin "2") (pinfunction "2_2") (pintype "passive"))
      (node (ref "U1") (pin "5") (pinfunction "SC0_5") (pintype "bidirectional"))
      (node (ref "X2") (pin "4") (pinfunction "S_4") (pintype "passive"))
    )
    (net (code "53") (name "SC1") (class "Default")
      (node (ref "R2") (pin "2") (pinfunction "2_2") (pintype "passive"))
      (node (ref "U1") (pin "7") (pinfunction "SC1_7") (pintype "bidirectional"))
      (node (ref "X3") (pin "4") (pinfunction "S_4") (pintype "passive"))
    )
    (net (code "54") (name "SC2") (class "Default")
      (node (ref "R4") (pin "2") (pinfunction "2_2") (pintype "passive"))
      (node (ref "U1") (pin "10") (pinfunction "SC2_10") (pintype "bidirectional"))
      (node (ref "X5") (pin "4") (pinfunction "S_4") (pintype "passive"))
    )
    (net (code "55") (name "SC3") (class "Default")
      (node (ref "R6") (pin "2") (pinfunction "2_2") (pintype "passive"))
      (node (ref "U1") (pin "12") (pinfunction "SC3_12") (pintype "bidirectional"))
      (node (ref "X6") (pin "4") (pinfunction "S_4") (pintype "passive"))
    )
    (net (code "56") (name "SC4") (class "Default")
      (node (ref "R8") (pin "2") (pinfunction "2_2") (pintype "passive"))
      (node (ref "U2") (pin "5") (pinfunction "SC0_5") (pintype "bidirectional"))
      (node (ref "X7") (pin "4") (pinfunction "S_4") (pintype "passive"))
    )
    (net (code "57") (name "SC5") (class "Default")
      (node (ref "R10") (pin "2") (pinfunction "2_2") (pintype "passive"))
      (node (ref "U2") (pin "7") (pinfunction "SC1_7") (pintype "bidirectional"))
      (node (ref "X8") (pin "4") (pinfunction "S_4") (pintype "passive"))
    )
    (net (code "58") (name "SC6") (class "Default")
      (node (ref "R12") (pin "2") (pinfunction "2_2") (pintype "passive"))
      (node (ref "U2") (pin "10") (pinfunction "SC2_10") (pintype "bidirectional"))
      (node (ref "X9") (pin "4") (pinfunction "S_4") (pintype "passive"))
    )
    (net (code "59") (name "SC7") (class "Default")
      (node (ref "R17") (pin "2") (pinfunction "2_2") (pintype "passive"))
      (node (ref "U2") (pin "12") (pinfunction "SC3_12") (pintype "bidirectional"))
      (node (ref "X10") (pin "4") (pinfunction "S_4") (pintype "passive"))
    )
    (net (code "60") (name "SC8") (class "Default")
      (node (ref "R19") (pin "2") (pinfunction "2_2") (pintype "passive"))
      (node (ref "U3") (pin "5") (pinfunction "SC0_5") (pintype "bidirectional"))
      (node (ref "X11") (pin "4") (pinfunction "S_4") (pintype "passive"))
    )
    (net (code "61") (name "SC9") (class "Default")
      (node (ref "R21") (pin "2") (pinfunction "2_2") (pintype "passive"))
      (node (ref "U3") (pin "7") (pinfunction "SC1_7") (pintype "bidirectional"))
      (node (ref "X12") (pin "4") (pinfunction "S_4") (pintype "passive"))
    )
    (net (code "62") (name "SC10") (class "Default")
      (node (ref "R24") (pin "2") (pinfunction "2_2") (pintype "passive"))
      (node (ref "U3") (pin "10") (pinfunction "SC2_10") (pintype "bidirectional"))
      (node (ref "X13") (pin "4") (pinfunction "S_4") (pintype "passive"))
    )
    (net (code "63") (name "SC11") (class "Default")
      (node (ref "R26") (pin "2") (pinfunction "2_2") (pintype "passive"))
      (node (ref "U3") (pin "12") (pinfunction "SC3_12") (pintype "bidirectional"))
      (node (ref "X14") (pin "4") (pinfunction "S_4") (pintype "passive"))
    )
    (net (code "64") (name "SCL2") (class "Default")
      (node (ref "U1") (pin "14") (pinfunction "SCL_14") (pintype "bidirectional"))
      (node (ref "U2") (pin "14") (pinfunction "SCL_14") (pintype "bidirectional"))
      (node (ref "U3") (pin "14") (pinfunction "SCL_14") (pintype "bidirectional"))
      (node (ref "X4") (pin "1") (pinfunction "S_1") (pintype "passive"))
    )
    (net (code "65") (name "SD0") (class "Default")
      (node (ref "R16") (pin "2") (pinfunction "2_2") (pintype "passive"))
      (node (ref "U1") (pin "4") (pinfunction "SD0_4") (pintype "bidirectional"))
      (node (ref "X2") (pin "3") (pinfunction "S_3") (pintype "passive"))
    )
    (net (code "66") (name "SD1") (class "Default")
      (node (ref "R1") (pin "2") (pinfunction "2_2") (pintype "passive"))
      (node (ref "U1") (pin "6") (pinfunction "SD1_6") (pintype "bidirectional"))
      (node (ref "X3") (pin "3") (pinfunction "S_3") (pintype "passive"))
    )
    (net (code "67") (name "SD2") (class "Default")
      (node (ref "R3") (pin "2") (pinfunction "2_2") (pintype "passive"))
      (node (ref "U1") (pin "9") (pinfunction "SD2_9") (pintype "bidirectional"))
      (node (ref "X5") (pin "3") (pinfunction "S_3") (pintype "passive"))
    )
    (net (code "68") (name "SD3") (class "Default")
      (node (ref "R5") (pin "2") (pinfunction "2_2") (pintype "passive"))
      (node (ref "U1") (pin "11") (pinfunction "SD3_11") (pintype "bidirectional"))
      (node (ref "X6") (pin "3") (pinfunction "S_3") (pintype "passive"))
    )
    (net (code "69") (name "SD4") (class "Default")
      (node (ref "R7") (pin "2") (pinfunction "2_2") (pintype "passive"))
      (node (ref "U2") (pin "4") (pinfunction "SD0_4") (pintype "bidirectional"))
      (node (ref "X7") (pin "3") (pinfunction "S_3") (pintype "passive"))
    )
    (net (code "70") (name "SD5") (class "Default")
      (node (ref "R9") (pin "2") (pinfunction "2_2") (pintype "passive"))
      (node (ref "U2") (pin "6") (pinfunction "SD1_6") (pintype "bidirectional"))
      (node (ref "X8") (pin "3") (pinfunction "S_3") (pintype "passive"))
    )
    (net (code "71") (name "SD6") (class "Default")
      (node (ref "R11") (pin "2") (pinfunction "2_2") (pintype "passive"))
      (node (ref "U2") (pin "9") (pinfunction "SD2_9") (pintype "bidirectional"))
      (node (ref "X9") (pin "3") (pinfunction "S_3") (pintype "passive"))
    )
    (net (code "72") (name "SD7") (class "Default")
      (node (ref "R13") (pin "2") (pinfunction "2_2") (pintype "passive"))
      (node (ref "U2") (pin "11") (pinfunction "SD3_11") (pintype "bidirectional"))
      (node (ref "X10") (pin "3") (pinfunction "S_3") (pintype "passive"))
    )
    (net (code "73") (name "SD8") (class "Default")
      (node (ref "R18") (pin "2") (pinfunction "2_2") (pintype "passive"))
      (node (ref "U3") (pin "4") (pinfunction "SD0_4") (pintype "bidirectional"))
      (node (ref "X11") (pin "3") (pinfunction "S_3") (pintype "passive"))
    )
    (net (code "74") (name "SD9") (class "Default")
      (node (ref "R20") (pin "2") (pinfunction "2_2") (pintype "passive"))
      (node (ref "U3") (pin "6") (pinfunction "SD1_6") (pintype "bidirectional"))
      (node (ref "X12") (pin "3") (pinfunction "S_3") (pintype "passive"))
    )
    (net (code "75") (name "SD10") (class "Default")
      (node (ref "R23") (pin "2") (pinfunction "2_2") (pintype "passive"))
      (node (ref "U3") (pin "9") (pinfunction "SD2_9") (pintype "bidirectional"))
      (node (ref "X13") (pin "3") (pinfunction "S_3") (pintype "passive"))
    )
    (net (code "76") (name "SD11") (class "Default")
      (node (ref "R25") (pin "2") (pinfunction "2_2") (pintype "passive"))
      (node (ref "U3") (pin "11") (pinfunction "SD3_11") (pintype "bidirectional"))
      (node (ref "X14") (pin "3") (pinfunction "S_3") (pintype "passive"))
    )
    (net (code "77") (name "SDA2") (class "Default")
      (node (ref "U1") (pin "15") (pinfunction "SDA_15") (pintype "bidirectional"))
      (node (ref "U2") (pin "15") (pinfunction "SDA_15") (pintype "bidirectional"))
      (node (ref "U3") (pin "15") (pinfunction "SDA_15") (pintype "bidirectional"))
      (node (ref "X4") (pin "2") (pinfunction "S_2") (pintype "passive"))
    )
    (net (code "78") (name "VDD") (class "Default")
      (node (ref "C1") (pin "1") (pinfunction "1_1") (pintype "passive"))
      (node (ref "C2") (pin "1") (pinfunction "1_1") (pintype "passive"))
      (node (ref "C21") (pin "1") (pinfunction "1_1") (pintype "passive"))
      (node (ref "R1") (pin "1") (pinfunction "1_1") (pintype "passive"))
      (node (ref "R10") (pin "1") (pinfunction "1_1") (pintype "passive"))
      (node (ref "R11") (pin "1") (pinfunction "1_1") (pintype "passive"))
      (node (ref "R12") (pin "1") (pinfunction "1_1") (pintype "passive"))
      (node (ref "R13") (pin "1") (pinfunction "1_1") (pintype "passive"))
      (node (ref "R14") (pin "1") (pinfunction "1_1") (pintype "passive"))
      (node (ref "R15") (pin "1") (pinfunction "1_1") (pintype "passive"))
      (node (ref "R16") (pin "1") (pinfunction "1_1") (pintype "passive"))
      (node (ref "R17") (pin "1") (pinfunction "1_1") (pintype "passive"))
      (node (ref "R18") (pin "1") (pinfunction "1_1") (pintype "passive"))
      (node (ref "R19") (pin "1") (pinfunction "1_1") (pintype "passive"))
      (node (ref "R2") (pin "1") (pinfunction "1_1") (pintype "passive"))
      (node (ref "R20") (pin "1") (pinfunction "1_1") (pintype "passive"))
      (node (ref "R21") (pin "1") (pinfunction "1_1") (pintype "passive"))
      (node (ref "R22") (pin "1") (pinfunction "1_1") (pintype "passive"))
      (node (ref "R23") (pin "1") (pinfunction "1_1") (pintype "passive"))
      (node (ref "R24") (pin "1") (pinfunction "1_1") (pintype "passive"))
      (node (ref "R25") (pin "1") (pinfunction "1_1") (pintype "passive"))
      (node (ref "R26") (pin "1") (pinfunction "1_1") (pintype "passive"))
      (node (ref "R27") (pin "1") (pinfunction "1_1") (pintype "passive"))
      (node (ref "R3") (pin "1") (pinfunction "1_1") (pintype "passive"))
      (node (ref "R4") (pin "1") (pinfunction "1_1") (pintype "passive"))
      (node (ref "R5") (pin "1") (pinfunction "1_1") (pintype "passive"))
      (node (ref "R6") (pin "1") (pinfunction "1_1") (pintype "passive"))
      (node (ref "R7") (pin "1") (pinfunction "1_1") (pintype "passive"))
      (node (ref "R8") (pin "1") (pinfunction "1_1") (pintype "passive"))
      (node (ref "R9") (pin "1") (pinfunction "1_1") (pintype "passive"))
      (node (ref "U1") (pin "16") (pinfunction "VDD_16") (pintype "bidirectional"))
      (node (ref "U2") (pin "1") (pinfunction "A0_1") (pintype "bidirectional"))
      (node (ref "U2") (pin "16") (pinfunction "VDD_16") (pintype "bidirectional"))
      (node (ref "U3") (pin "16") (pinfunction "VDD_16") (pintype "bidirectional"))
      (node (ref "U3") (pin "2") (pinfunction "A1_2") (pintype "bidirectional"))
      (node (ref "X1") (pin "1") (pinfunction "S_1") (pintype "passive"))
    )
    (net (code "79") (name "VLASER") (class "Default")
      (node (ref "C11") (pin "1") (pinfunction "1_1") (pintype "passive"))
      (node (ref "C13") (pin "1") (pinfunction "1_1") (pintype "passive"))
      (node (ref "C15") (pin "1") (pinfunction "1_1") (pintype "passive"))
      (node (ref "C17") (pin "1") (pinfunction "1_1") (pintype "passive"))
      (node (ref "C19") (pin "1") (pinfunction "1_1") (pintype "passive"))
      (node (ref "C22") (pin "1") (pinfunction "1_1") (pintype "passive"))
      (node (ref "C24") (pin "1") (pinfunction "1_1") (pintype "passive"))
      (node (ref "C26") (pin "1") (pinfunction "1_1") (pintype "passive"))
      (node (ref "C3") (pin "1") (pinfunction "1_1") (pintype "passive"))
      (node (ref "C5") (pin "1") (pinfunction "1_1") (pintype "passive"))
      (node (ref "C7") (pin "1") (pinfunction "1_1") (pintype "passive"))
      (node (ref "C9") (pin "1") (pinfunction "1_1") (pintype "passive"))
      (node (ref "U10") (pin "1") (pinfunction "P$1_1") (pintype "bidirectional"))
      (node (ref "U11") (pin "1") (pinfunction "P$1_1") (pintype "bidirectional"))
      (node (ref "U12") (pin "1") (pinfunction "P$1_1") (pintype "bidirectional"))
      (node (ref "U13") (pin "1") (pinfunction "P$1_1") (pintype "bidirectional"))
      (node (ref "U14") (pin "1") (pinfunction "P$1_1") (pintype "bidirectional"))
      (node (ref "U15") (pin "1") (pinfunction "P$1_1") (pintype "bidirectional"))
      (node (ref "U4") (pin "1") (pinfunction "P$1_1") (pintype "bidirectional"))
      (node (ref "U5") (pin "1") (pinfunction "P$1_1") (pintype "bidirectional"))
      (node (ref "U6") (pin "1") (pinfunction "P$1_1") (pintype "bidirectional"))
      (node (ref "U7") (pin "1") (pinfunction "P$1_1") (pintype "bidirectional"))
      (node (ref "U8") (pin "1") (pinfunction "P$1_1") (pintype "bidirectional"))
      (node (ref "U9") (pin "1") (pinfunction "P$1_1") (pintype "bidirectional"))
      (node (ref "X4") (pin "4") (pinfunction "S_4") (pintype "passive"))
    )
    (net (code "80") (name "VTS") (class "Default")
      (node (ref "X1") (pin "2") (pinfunction "S_2") (pintype "passive"))
      (node (ref "X10") (pin "2") (pinfunction "S_2") (pintype "passive"))
      (node (ref "X11") (pin "2") (pinfunction "S_2") (pintype "passive"))
      (node (ref "X12") (pin "2") (pinfunction "S_2") (pintype "passive"))
      (node (ref "X13") (pin "2") (pinfunction "S_2") (pintype "passive"))
      (node (ref "X14") (pin "2") (pinfunction "S_2") (pintype "passive"))
      (node (ref "X2") (pin "2") (pinfunction "S_2") (pintype "passive"))
      (node (ref "X3") (pin "2") (pinfunction "S_2") (pintype "passive"))
      (node (ref "X5") (pin "2") (pinfunction "S_2") (pintype "passive"))
      (node (ref "X6") (pin "2") (pinfunction "S_2") (pintype "passive"))
      (node (ref "X7") (pin "2") (pinfunction "S_2") (pintype "passive"))
      (node (ref "X8") (pin "2") (pinfunction "S_2") (pintype "passive"))
      (node (ref "X9") (pin "2") (pinfunction "S_2") (pintype "passive"))
    )
    (net (code "81") (name "unconnected-(J1A-S-Pad2)") (class "Default")
      (node (ref "J1") (pin "2") (pinfunction "S_2") (pintype "passive"))
    )
    (net (code "82") (name "unconnected-(J2A-S-Pad2)") (class "Default")
      (node (ref "J2") (pin "2") (pinfunction "S_2") (pintype "passive"))
    )
    (net (code "83") (name "unconnected-(J3A-S-Pad2)") (class "Default")
      (node (ref "J3") (pin "2") (pinfunction "S_2") (pintype "passive"))
    )
    (net (code "84") (name "unconnected-(J4A-S-Pad2)") (class "Default")
      (node (ref "J4") (pin "2") (pinfunction "S_2") (pintype "passive"))
    )
    (net (code "85") (name "unconnected-(J5A-S-Pad2)") (class "Default")
      (node (ref "J5") (pin "2") (pinfunction "S_2") (pintype "passive"))
    )
    (net (code "86") (name "unconnected-(J6A-S-Pad2)") (class "Default")
      (node (ref "J6") (pin "2") (pinfunction "S_2") (pintype "passive"))
    )
    (net (code "87") (name "unconnected-(J7A-S-Pad2)") (class "Default")
      (node (ref "J7") (pin "2") (pinfunction "S_2") (pintype "passive"))
    )
    (net (code "88") (name "unconnected-(J8A-S-Pad2)") (class "Default")
      (node (ref "J8") (pin "2") (pinfunction "S_2") (pintype "passive"))
    )
    (net (code "89") (name "unconnected-(J9A-S-Pad2)") (class "Default")
      (node (ref "J9") (pin "2") (pinfunction "S_2") (pintype "passive"))
    )
    (net (code "90") (name "unconnected-(J10A-S-Pad2)") (class "Default")
      (node (ref "J10") (pin "2") (pinfunction "S_2") (pintype "passive"))
    )
    (net (code "91") (name "unconnected-(J11A-S-Pad2)") (class "Default")
      (node (ref "J11") (pin "2") (pinfunction "S_2") (pintype "passive"))
    )
    (net (code "92") (name "unconnected-(J12A-S-Pad2)") (class "Default")
      (node (ref "J12") (pin "2") (pinfunction "S_2") (pintype "passive"))
    )
  )
)
